# PS_DDR4.net
KiCad netlist of a schematic drawn in Altium Designer
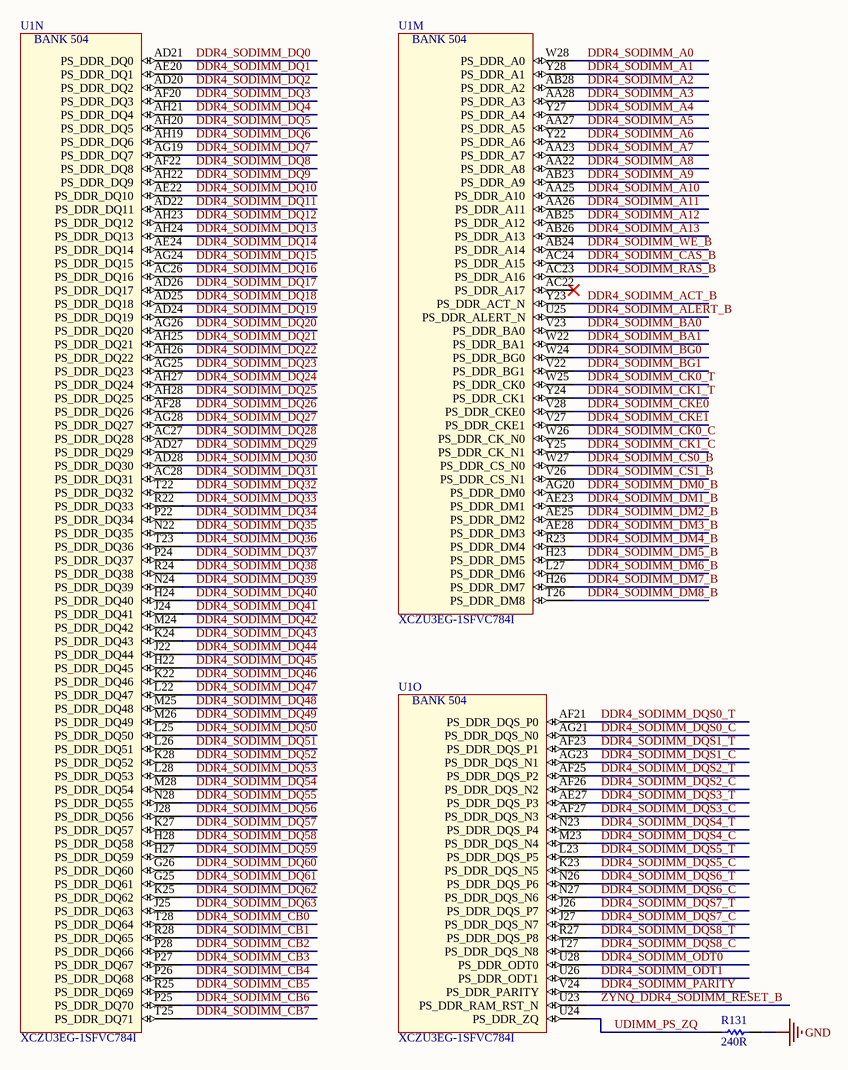
[diagram p0: PS_DDR4.SchDoc]

(export (version "E")
  (design (tool "Eeschema 10.0.6"))
  (components
    (comp (ref "R131")
      (value "240R")
      (footprint "RESC1005L_0402")
      (description "RES SMD 240 OHM 1% 1/10W 0402")
      (fields (field (name "POWER") "1/10W") (field (name "TOLERANCE") "1%"))
      (libsource (lib "Ultrascale_SchLib") (part "RES0402_240R_0W1_1T"))
    )
    (comp (ref "U1")
      (value "XCZU3EG-1SFVC784I")
      (footprint "BGA784x28")
      (description "IC FPGA 252 I/O 784FCBGA - XILINX ZYNQ ULTRASCALE+")
      (libsource (lib "Ultrascale_SchLib") (part "XCZU3EG-1SFVC784I"))
    )
  )
  (nets
    (net (code "1") (name "/DDR4_SODIMM_A0") (class "Default")
      (node (ref "U1") (pin "W28") (pinfunction "PS_DDR_A0_W28") (pintype "bidirectional"))
    )
    (net (code "2") (name "/DDR4_SODIMM_A1") (class "Default")
      (node (ref "U1") (pin "Y28") (pinfunction "PS_DDR_A1_Y28") (pintype "bidirectional"))
    )
    (net (code "3") (name "/DDR4_SODIMM_A2") (class "Default")
      (node (ref "U1") (pin "AB28") (pinfunction "PS_DDR_A2_AB28") (pintype "bidirectional"))
    )
    (net (code "4") (name "/DDR4_SODIMM_A3") (class "Default")
      (node (ref "U1") (pin "AA28") (pinfunction "PS_DDR_A3_AA28") (pintype "bidirectional"))
    )
    (net (code "5") (name "/DDR4_SODIMM_A4") (class "Default")
      (node (ref "U1") (pin "Y27") (pinfunction "PS_DDR_A4_Y27") (pintype "bidirectional"))
    )
    (net (code "6") (name "/DDR4_SODIMM_A5") (class "Default")
      (node (ref "U1") (pin "AA27") (pinfunction "PS_DDR_A5_AA27") (pintype "bidirectional"))
    )
    (net (code "7") (name "/DDR4_SODIMM_A6") (class "Default")
      (node (ref "U1") (pin "Y22") (pinfunction "PS_DDR_A6_Y22") (pintype "bidirectional"))
    )
    (net (code "8") (name "/DDR4_SODIMM_A7") (class "Default")
      (node (ref "U1") (pin "AA23") (pinfunction "PS_DDR_A7_AA23") (pintype "bidirectional"))
    )
    (net (code "9") (name "/DDR4_SODIMM_A8") (class "Default")
      (node (ref "U1") (pin "AA22") (pinfunction "PS_DDR_A8_AA22") (pintype "bidirectional"))
    )
    (net (code "10") (name "/DDR4_SODIMM_A9") (class "Default")
      (node (ref "U1") (pin "AB23") (pinfunction "PS_DDR_A9_AB23") (pintype "bidirectional"))
    )
    (net (code "11") (name "/DDR4_SODIMM_A10") (class "Default")
      (node (ref "U1") (pin "AA25") (pinfunction "PS_DDR_A10_AA25") (pintype "bidirectional"))
    )
    (net (code "12") (name "/DDR4_SODIMM_A11") (class "Default")
      (node (ref "U1") (pin "AA26") (pinfunction "PS_DDR_A11_AA26") (pintype "bidirectional"))
    )
    (net (code "13") (name "/DDR4_SODIMM_A12") (class "Default")
      (node (ref "U1") (pin "AB25") (pinfunction "PS_DDR_A12_AB25") (pintype "bidirectional"))
    )
    (net (code "14") (name "/DDR4_SODIMM_A13") (class "Default")
      (node (ref "U1") (pin "AB26") (pinfunction "PS_DDR_A13_AB26") (pintype "bidirectional"))
    )
    (net (code "15") (name "/DDR4_SODIMM_ACT_B") (class "Default")
      (node (ref "U1") (pin "Y23") (pinfunction "PS_DDR_ACT_N_Y23") (pintype "bidirectional"))
    )
    (net (code "16") (name "/DDR4_SODIMM_ALERT_B") (class "Default")
      (node (ref "U1") (pin "U25") (pinfunction "PS_DDR_ALERT_N_U25") (pintype "bidirectional"))
    )
    (net (code "17") (name "/DDR4_SODIMM_BA0") (class "Default")
      (node (ref "U1") (pin "V23") (pinfunction "PS_DDR_BA0_V23") (pintype "bidirectional"))
    )
    (net (code "18") (name "/DDR4_SODIMM_BA1") (class "Default")
      (node (ref "U1") (pin "W22") (pinfunction "PS_DDR_BA1_W22") (pintype "bidirectional"))
    )
    (net (code "19") (name "/DDR4_SODIMM_BG0") (class "Default")
      (node (ref "U1") (pin "W24") (pinfunction "PS_DDR_BG0_W24") (pintype "bidirectional"))
    )
    (net (code "20") (name "/DDR4_SODIMM_BG1") (class "Default")
      (node (ref "U1") (pin "V22") (pinfunction "PS_DDR_BG1_V22") (pintype "bidirectional"))
    )
    (net (code "21") (name "/DDR4_SODIMM_CAS_B") (class "Default")
      (node (ref "U1") (pin "AC24") (pinfunction "PS_DDR_A15_AC24") (pintype "bidirectional"))
    )
    (net (code "22") (name "/DDR4_SODIMM_CB0") (class "Default")
      (node (ref "U1") (pin "T28") (pinfunction "PS_DDR_DQ64_T28") (pintype "bidirectional"))
    )
    (net (code "23") (name "/DDR4_SODIMM_CB1") (class "Default")
      (node (ref "U1") (pin "R28") (pinfunction "PS_DDR_DQ65_R28") (pintype "bidirectional"))
    )
    (net (code "24") (name "/DDR4_SODIMM_CB2") (class "Default")
      (node (ref "U1") (pin "P28") (pinfunction "PS_DDR_DQ66_P28") (pintype "bidirectional"))
    )
    (net (code "25") (name "/DDR4_SODIMM_CB3") (class "Default")
      (node (ref "U1") (pin "P27") (pinfunction "PS_DDR_DQ67_P27") (pintype "bidirectional"))
    )
    (net (code "26") (name "/DDR4_SODIMM_CB4") (class "Default")
      (node (ref "U1") (pin "P26") (pinfunction "PS_DDR_DQ68_P26") (pintype "bidirectional"))
    )
    (net (code "27") (name "/DDR4_SODIMM_CB5") (class "Default")
      (node (ref "U1") (pin "R25") (pinfunction "PS_DDR_DQ69_R25") (pintype "bidirectional"))
    )
    (net (code "28") (name "/DDR4_SODIMM_CB6") (class "Default")
      (node (ref "U1") (pin "P25") (pinfunction "PS_DDR_DQ70_P25") (pintype "bidirectional"))
    )
    (net (code "29") (name "/DDR4_SODIMM_CB7") (class "Default")
      (node (ref "U1") (pin "T25") (pinfunction "PS_DDR_DQ71_T25") (pintype "bidirectional"))
    )
    (net (code "30") (name "/DDR4_SODIMM_CK0_C") (class "Default")
      (node (ref "U1") (pin "W26") (pinfunction "PS_DDR_CK_N0_W26") (pintype "bidirectional"))
    )
    (net (code "31") (name "/DDR4_SODIMM_CK0_T") (class "Default")
      (node (ref "U1") (pin "W25") (pinfunction "PS_DDR_CK0_W25") (pintype "bidirectional"))
    )
    (net (code "32") (name "/DDR4_SODIMM_CK1_C") (class "Default")
      (node (ref "U1") (pin "Y25") (pinfunction "PS_DDR_CK_N1_Y25") (pintype "bidirectional"))
    )
    (net (code "33") (name "/DDR4_SODIMM_CK1_T") (class "Default")
      (node (ref "U1") (pin "Y24") (pinfunction "PS_DDR_CK1_Y24") (pintype "bidirectional"))
    )
    (net (code "34") (name "/DDR4_SODIMM_CKE0") (class "Default")
      (node (ref "U1") (pin "V28") (pinfunction "PS_DDR_CKE0_V28") (pintype "bidirectional"))
    )
    (net (code "35") (name "/DDR4_SODIMM_CKE1") (class "Default")
      (node (ref "U1") (pin "V27") (pinfunction "PS_DDR_CKE1_V27") (pintype "bidirectional"))
    )
    (net (code "36") (name "/DDR4_SODIMM_CS0_B") (class "Default")
      (node (ref "U1") (pin "W27") (pinfunction "PS_DDR_CS_N0_W27") (pintype "bidirectional"))
    )
    (net (code "37") (name "/DDR4_SODIMM_CS1_B") (class "Default")
      (node (ref "U1") (pin "V26") (pinfunction "PS_DDR_CS_N1_V26") (pintype "bidirectional"))
    )
    (net (code "38") (name "/DDR4_SODIMM_DM0_B") (class "Default")
      (node (ref "U1") (pin "AG20") (pinfunction "PS_DDR_DM0_AG20") (pintype "bidirectional"))
    )
    (net (code "39") (name "/DDR4_SODIMM_DM1_B") (class "Default")
      (node (ref "U1") (pin "AE23") (pinfunction "PS_DDR_DM1_AE23") (pintype "bidirectional"))
    )
    (net (code "40") (name "/DDR4_SODIMM_DM2_B") (class "Default")
      (node (ref "U1") (pin "AE25") (pinfunction "PS_DDR_DM2_AE25") (pintype "bidirectional"))
    )
    (net (code "41") (name "/DDR4_SODIMM_DM3_B") (class "Default")
      (node (ref "U1") (pin "AE28") (pinfunction "PS_DDR_DM3_AE28") (pintype "bidirectional"))
    )
    (net (code "42") (name "/DDR4_SODIMM_DM4_B") (class "Default")
      (node (ref "U1") (pin "R23") (pinfunction "PS_DDR_DM4_R23") (pintype "bidirectional"))
    )
    (net (code "43") (name "/DDR4_SODIMM_DM5_B") (class "Default")
      (node (ref "U1") (pin "H23") (pinfunction "PS_DDR_DM5_H23") (pintype "bidirectional"))
    )
    (net (code "44") (name "/DDR4_SODIMM_DM6_B") (class "Default")
      (node (ref "U1") (pin "L27") (pinfunction "PS_DDR_DM6_L27") (pintype "bidirectional"))
    )
    (net (code "45") (name "/DDR4_SODIMM_DM7_B") (class "Default")
      (node (ref "U1") (pin "H26") (pinfunction "PS_DDR_DM7_H26") (pintype "bidirectional"))
    )
    (net (code "46") (name "/DDR4_SODIMM_DM8_B") (class "Default")
      (node (ref "U1") (pin "T26") (pinfunction "PS_DDR_DM8_T26") (pintype "bidirectional"))
    )
    (net (code "47") (name "/DDR4_SODIMM_DQ0") (class "Default")
      (node (ref "U1") (pin "AD21") (pinfunction "PS_DDR_DQ0_AD21") (pintype "bidirectional"))
    )
    (net (code "48") (name "/DDR4_SODIMM_DQ1") (class "Default")
      (node (ref "U1") (pin "AE20") (pinfunction "PS_DDR_DQ1_AE20") (pintype "bidirectional"))
    )
    (net (code "49") (name "/DDR4_SODIMM_DQ2") (class "Default")
      (node (ref "U1") (pin "AD20") (pinfunction "PS_DDR_DQ2_AD20") (pintype "bidirectional"))
    )
    (net (code "50") (name "/DDR4_SODIMM_DQ3") (class "Default")
      (node (ref "U1") (pin "AF20") (pinfunction "PS_DDR_DQ3_AF20") (pintype "bidirectional"))
    )
    (net (code "51") (name "/DDR4_SODIMM_DQ4") (class "Default")
      (node (ref "U1") (pin "AH21") (pinfunction "PS_DDR_DQ4_AH21") (pintype "bidirectional"))
    )
    (net (code "52") (name "/DDR4_SODIMM_DQ5") (class "Default")
      (node (ref "U1") (pin "AH20") (pinfunction "PS_DDR_DQ5_AH20") (pintype "bidirectional"))
    )
    (net (code "53") (name "/DDR4_SODIMM_DQ6") (class "Default")
      (node (ref "U1") (pin "AH19") (pinfunction "PS_DDR_DQ6_AH19") (pintype "bidirectional"))
    )
    (net (code "54") (name "/DDR4_SODIMM_DQ7") (class "Default")
      (node (ref "U1") (pin "AG19") (pinfunction "PS_DDR_DQ7_AG19") (pintype "bidirectional"))
    )
    (net (code "55") (name "/DDR4_SODIMM_DQ8") (class "Default")
      (node (ref "U1") (pin "AF22") (pinfunction "PS_DDR_DQ8_AF22") (pintype "bidirectional"))
    )
    (net (code "56") (name "/DDR4_SODIMM_DQ9") (class "Default")
      (node (ref "U1") (pin "AH22") (pinfunction "PS_DDR_DQ9_AH22") (pintype "bidirectional"))
    )
    (net (code "57") (name "/DDR4_SODIMM_DQ10") (class "Default")
      (node (ref "U1") (pin "AE22") (pinfunction "PS_DDR_DQ10_AE22") (pintype "bidirectional"))
    )
    (net (code "58") (name "/DDR4_SODIMM_DQ11") (class "Default")
      (node (ref "U1") (pin "AD22") (pinfunction "PS_DDR_DQ11_AD22") (pintype "bidirectional"))
    )
    (net (code "59") (name "/DDR4_SODIMM_DQ12") (class "Default")
      (node (ref "U1") (pin "AH23") (pinfunction "PS_DDR_DQ12_AH23") (pintype "bidirectional"))
    )
    (net (code "60") (name "/DDR4_SODIMM_DQ13") (class "Default")
      (node (ref "U1") (pin "AH24") (pinfunction "PS_DDR_DQ13_AH24") (pintype "bidirectional"))
    )
    (net (code "61") (name "/DDR4_SODIMM_DQ14") (class "Default")
      (node (ref "U1") (pin "AE24") (pinfunction "PS_DDR_DQ14_AE24") (pintype "bidirectional"))
    )
    (net (code "62") (name "/DDR4_SODIMM_DQ15") (class "Default")
      (node (ref "U1") (pin "AG24") (pinfunction "PS_DDR_DQ15_AG24") (pintype "bidirectional"))
    )
    (net (code "63") (name "/DDR4_SODIMM_DQ16") (class "Default")
      (node (ref "U1") (pin "AC26") (pinfunction "PS_DDR_DQ16_AC26") (pintype "bidirectional"))
    )
    (net (code "64") (name "/DDR4_SODIMM_DQ17") (class "Default")
      (node (ref "U1") (pin "AD26") (pinfunction "PS_DDR_DQ17_AD26") (pintype "bidirectional"))
    )
    (net (code "65") (name "/DDR4_SODIMM_DQ18") (class "Default")
      (node (ref "U1") (pin "AD25") (pinfunction "PS_DDR_DQ18_AD25") (pintype "bidirectional"))
    )
    (net (code "66") (name "/DDR4_SODIMM_DQ19") (class "Default")
      (node (ref "U1") (pin "AD24") (pinfunction "PS_DDR_DQ19_AD24") (pintype "bidirectional"))
    )
    (net (code "67") (name "/DDR4_SODIMM_DQ20") (class "Default")
      (node (ref "U1") (pin "AG26") (pinfunction "PS_DDR_DQ20_AG26") (pintype "bidirectional"))
    )
    (net (code "68") (name "/DDR4_SODIMM_DQ21") (class "Default")
      (node (ref "U1") (pin "AH25") (pinfunction "PS_DDR_DQ21_AH25") (pintype "bidirectional"))
    )
    (net (code "69") (name "/DDR4_SODIMM_DQ22") (class "Default")
      (node (ref "U1") (pin "AH26") (pinfunction "PS_DDR_DQ22_AH26") (pintype "bidirectional"))
    )
    (net (code "70") (name "/DDR4_SODIMM_DQ23") (class "Default")
      (node (ref "U1") (pin "AG25") (pinfunction "PS_DDR_DQ23_AG25") (pintype "bidirectional"))
    )
    (net (code "71") (name "/DDR4_SODIMM_DQ24") (class "Default")
      (node (ref "U1") (pin "AH27") (pinfunction "PS_DDR_DQ24_AH27") (pintype "bidirectional"))
    )
    (net (code "72") (name "/DDR4_SODIMM_DQ25") (class "Default")
      (node (ref "U1") (pin "AH28") (pinfunction "PS_DDR_DQ25_AH28") (pintype "bidirectional"))
    )
    (net (code "73") (name "/DDR4_SODIMM_DQ26") (class "Default")
      (node (ref "U1") (pin "AF28") (pinfunction "PS_DDR_DQ26_AF28") (pintype "bidirectional"))
    )
    (net (code "74") (name "/DDR4_SODIMM_DQ27") (class "Default")
      (node (ref "U1") (pin "AG28") (pinfunction "PS_DDR_DQ27_AG28") (pintype "bidirectional"))
    )
    (net (code "75") (name "/DDR4_SODIMM_DQ28") (class "Default")
      (node (ref "U1") (pin "AC27") (pinfunction "PS_DDR_DQ28_AC27") (pintype "bidirectional"))
    )
    (net (code "76") (name "/DDR4_SODIMM_DQ29") (class "Default")
      (node (ref "U1") (pin "AD27") (pinfunction "PS_DDR_DQ29_AD27") (pintype "bidirectional"))
    )
    (net (code "77") (name "/DDR4_SODIMM_DQ30") (class "Default")
      (node (ref "U1") (pin "AD28") (pinfunction "PS_DDR_DQ30_AD28") (pintype "bidirectional"))
    )
    (net (code "78") (name "/DDR4_SODIMM_DQ31") (class "Default")
      (node (ref "U1") (pin "AC28") (pinfunction "PS_DDR_DQ31_AC28") (pintype "bidirectional"))
    )
    (net (code "79") (name "/DDR4_SODIMM_DQ32") (class "Default")
      (node (ref "U1") (pin "T22") (pinfunction "PS_DDR_DQ32_T22") (pintype "bidirectional"))
    )
    (net (code "80") (name "/DDR4_SODIMM_DQ33") (class "Default")
      (node (ref "U1") (pin "R22") (pinfunction "PS_DDR_DQ33_R22") (pintype "bidirectional"))
    )
    (net (code "81") (name "/DDR4_SODIMM_DQ34") (class "Default")
      (node (ref "U1") (pin "P22") (pinfunction "PS_DDR_DQ34_P22") (pintype "bidirectional"))
    )
    (net (code "82") (name "/DDR4_SODIMM_DQ35") (class "Default")
      (node (ref "U1") (pin "N22") (pinfunction "PS_DDR_DQ35_N22") (pintype "bidirectional"))
    )
    (net (code "83") (name "/DDR4_SODIMM_DQ36") (class "Default")
      (node (ref "U1") (pin "T23") (pinfunction "PS_DDR_DQ36_T23") (pintype "bidirectional"))
    )
    (net (code "84") (name "/DDR4_SODIMM_DQ37") (class "Default")
      (node (ref "U1") (pin "P24") (pinfunction "PS_DDR_DQ37_P24") (pintype "bidirectional"))
    )
    (net (code "85") (name "/DDR4_SODIMM_DQ38") (class "Default")
      (node (ref "U1") (pin "R24") (pinfunction "PS_DDR_DQ38_R24") (pintype "bidirectional"))
    )
    (net (code "86") (name "/DDR4_SODIMM_DQ39") (class "Default")
      (node (ref "U1") (pin "N24") (pinfunction "PS_DDR_DQ39_N24") (pintype "bidirectional"))
    )
    (net (code "87") (name "/DDR4_SODIMM_DQ40") (class "Default")
      (node (ref "U1") (pin "H24") (pinfunction "PS_DDR_DQ40_H24") (pintype "bidirectional"))
    )
    (net (code "88") (name "/DDR4_SODIMM_DQ41") (class "Default")
      (node (ref "U1") (pin "J24") (pinfunction "PS_DDR_DQ41_J24") (pintype "bidirectional"))
    )
    (net (code "89") (name "/DDR4_SODIMM_DQ42") (class "Default")
      (node (ref "U1") (pin "M24") (pinfunction "PS_DDR_DQ42_M24") (pintype "bidirectional"))
    )
    (net (code "90") (name "/DDR4_SODIMM_DQ43") (class "Default")
      (node (ref "U1") (pin "K24") (pinfunction "PS_DDR_DQ43_K24") (pintype "bidirectional"))
    )
    (net (code "91") (name "/DDR4_SODIMM_DQ44") (class "Default")
      (node (ref "U1") (pin "J22") (pinfunction "PS_DDR_DQ44_J22") (pintype "bidirectional"))
    )
    (net (code "92") (name "/DDR4_SODIMM_DQ45") (class "Default")
      (node (ref "U1") (pin "H22") (pinfunction "PS_DDR_DQ45_H22") (pintype "bidirectional"))
    )
    (net (code "93") (name "/DDR4_SODIMM_DQ46") (class "Default")
      (node (ref "U1") (pin "K22") (pinfunction "PS_DDR_DQ46_K22") (pintype "bidirectional"))
    )
    (net (code "94") (name "/DDR4_SODIMM_DQ47") (class "Default")
      (node (ref "U1") (pin "L22") (pinfunction "PS_DDR_DQ47_L22") (pintype "bidirectional"))
    )
    (net (code "95") (name "/DDR4_SODIMM_DQ48") (class "Default")
      (node (ref "U1") (pin "M25") (pinfunction "PS_DDR_DQ48_M25") (pintype "bidirectional"))
    )
    (net (code "96") (name "/DDR4_SODIMM_DQ49") (class "Default")
      (node (ref "U1") (pin "M26") (pinfunction "PS_DDR_DQ49_M26") (pintype "bidirectional"))
    )
    (net (code "97") (name "/DDR4_SODIMM_DQ50") (class "Default")
      (node (ref "U1") (pin "L25") (pinfunction "PS_DDR_DQ50_L25") (pintype "bidirectional"))
    )
    (net (code "98") (name "/DDR4_SODIMM_DQ51") (class "Default")
      (node (ref "U1") (pin "L26") (pinfunction "PS_DDR_DQ51_L26") (pintype "bidirectional"))
    )
    (net (code "99") (name "/DDR4_SODIMM_DQ52") (class "Default")
      (node (ref "U1") (pin "K28") (pinfunction "PS_DDR_DQ52_K28") (pintype "bidirectional"))
    )
    (net (code "100") (name "/DDR4_SODIMM_DQ53") (class "Default")
      (node (ref "U1") (pin "L28") (pinfunction "PS_DDR_DQ53_L28") (pintype "bidirectional"))
    )
    (net (code "101") (name "/DDR4_SODIMM_DQ54") (class "Default")
      (node (ref "U1") (pin "M28") (pinfunction "PS_DDR_DQ54_M28") (pintype "bidirectional"))
    )
    (net (code "102") (name "/DDR4_SODIMM_DQ55") (class "Default")
      (node (ref "U1") (pin "N28") (pinfunction "PS_DDR_DQ55_N28") (pintype "bidirectional"))
    )
    (net (code "103") (name "/DDR4_SODIMM_DQ56") (class "Default")
      (node (ref "U1") (pin "J28") (pinfunction "PS_DDR_DQ56_J28") (pintype "bidirectional"))
    )
    (net (code "104") (name "/DDR4_SODIMM_DQ57") (class "Default")
      (node (ref "U1") (pin "K27") (pinfunction "PS_DDR_DQ57_K27") (pintype "bidirectional"))
    )
    (net (code "105") (name "/DDR4_SODIMM_DQ58") (class "Default")
      (node (ref "U1") (pin "H28") (pinfunction "PS_DDR_DQ58_H28") (pintype "bidirectional"))
    )
    (net (code "106") (name "/DDR4_SODIMM_DQ59") (class "Default")
      (node (ref "U1") (pin "H27") (pinfunction "PS_DDR_DQ59_H27") (pintype "bidirectional"))
    )
    (net (code "107") (name "/DDR4_SODIMM_DQ60") (class "Default")
      (node (ref "U1") (pin "G26") (pinfunction "PS_DDR_DQ60_G26") (pintype "bidirectional"))
    )
    (net (code "108") (name "/DDR4_SODIMM_DQ61") (class "Default")
      (node (ref "U1") (pin "G25") (pinfunction "PS_DDR_DQ61_G25") (pintype "bidirectional"))
    )
    (net (code "109") (name "/DDR4_SODIMM_DQ62") (class "Default")
      (node (ref "U1") (pin "K25") (pinfunction "PS_DDR_DQ62_K25") (pintype "bidirectional"))
    )
    (net (code "110") (name "/DDR4_SODIMM_DQ63") (class "Default")
      (node (ref "U1") (pin "J25") (pinfunction "PS_DDR_DQ63_J25") (pintype "bidirectional"))
    )
    (net (code "111") (name "/DDR4_SODIMM_DQS0_C") (class "Default")
      (node (ref "U1") (pin "AG21") (pinfunction "PS_DDR_DQS_N0_AG21") (pintype "bidirectional"))
    )
    (net (code "112") (name "/DDR4_SODIMM_DQS0_T") (class "Default")
      (node (ref "U1") (pin "AF21") (pinfunction "PS_DDR_DQS_P0_AF21") (pintype "bidirectional"))
    )
    (net (code "113") (name "/DDR4_SODIMM_DQS1_C") (class "Default")
      (node (ref "U1") (pin "AG23") (pinfunction "PS_DDR_DQS_N1_AG23") (pintype "bidirectional"))
    )
    (net (code "114") (name "/DDR4_SODIMM_DQS1_T") (class "Default")
      (node (ref "U1") (pin "AF23") (pinfunction "PS_DDR_DQS_P1_AF23") (pintype "bidirectional"))
    )
    (net (code "115") (name "/DDR4_SODIMM_DQS2_C") (class "Default")
      (node (ref "U1") (pin "AF26") (pinfunction "PS_DDR_DQS_N2_AF26") (pintype "bidirectional"))
    )
    (net (code "116") (name "/DDR4_SODIMM_DQS2_T") (class "Default")
      (node (ref "U1") (pin "AF25") (pinfunction "PS_DDR_DQS_P2_AF25") (pintype "bidirectional"))
    )
    (net (code "117") (name "/DDR4_SODIMM_DQS3_C") (class "Default")
      (node (ref "U1") (pin "AF27") (pinfunction "PS_DDR_DQS_N3_AF27") (pintype "bidirectional"))
    )
    (net (code "118") (name "/DDR4_SODIMM_DQS3_T") (class "Default")
      (node (ref "U1") (pin "AE27") (pinfunction "PS_DDR_DQS_P3_AE27") (pintype "bidirectional"))
    )
    (net (code "119") (name "/DDR4_SODIMM_DQS4_C") (class "Default")
      (node (ref "U1") (pin "M23") (pinfunction "PS_DDR_DQS_N4_M23") (pintype "bidirectional"))
    )
    (net (code "120") (name "/DDR4_SODIMM_DQS4_T") (class "Default")
      (node (ref "U1") (pin "N23") (pinfunction "PS_DDR_DQS_P4_N23") (pintype "bidirectional"))
    )
    (net (code "121") (name "/DDR4_SODIMM_DQS5_C") (class "Default")
      (node (ref "U1") (pin "K23") (pinfunction "PS_DDR_DQS_N5_K23") (pintype "bidirectional"))
    )
    (net (code "122") (name "/DDR4_SODIMM_DQS5_T") (class "Default")
      (node (ref "U1") (pin "L23") (pinfunction "PS_DDR_DQS_P5_L23") (pintype "bidirectional"))
    )
    (net (code "123") (name "/DDR4_SODIMM_DQS6_C") (class "Default")
      (node (ref "U1") (pin "N27") (pinfunction "PS_DDR_DQS_N6_N27") (pintype "bidirectional"))
    )
    (net (code "124") (name "/DDR4_SODIMM_DQS6_T") (class "Default")
      (node (ref "U1") (pin "N26") (pinfunction "PS_DDR_DQS_P6_N26") (pintype "bidirectional"))
    )
    (net (code "125") (name "/DDR4_SODIMM_DQS7_C") (class "Default")
      (node (ref "U1") (pin "J27") (pinfunction "PS_DDR_DQS_N7_J27") (pintype "bidirectional"))
    )
    (net (code "126") (name "/DDR4_SODIMM_DQS7_T") (class "Default")
      (node (ref "U1") (pin "J26") (pinfunction "PS_DDR_DQS_P7_J26") (pintype "bidirectional"))
    )
    (net (code "127") (name "/DDR4_SODIMM_DQS8_C") (class "Default")
      (node (ref "U1") (pin "T27") (pinfunction "PS_DDR_DQS_N8_T27") (pintype "bidirectional"))
    )
    (net (code "128") (name "/DDR4_SODIMM_DQS8_T") (class "Default")
      (node (ref "U1") (pin "R27") (pinfunction "PS_DDR_DQS_P8_R27") (pintype "bidirectional"))
    )
    (net (code "129") (name "/DDR4_SODIMM_ODT0") (class "Default")
      (node (ref "U1") (pin "U28") (pinfunction "PS_DDR_ODT0_U28") (pintype "bidirectional"))
    )
    (net (code "130") (name "/DDR4_SODIMM_ODT1") (class "Default")
      (node (ref "U1") (pin "U26") (pinfunction "PS_DDR_ODT1_U26") (pintype "bidirectional"))
    )
    (net (code "131") (name "/DDR4_SODIMM_PARITY") (class "Default")
      (node (ref "U1") (pin "V24") (pinfunction "PS_DDR_PARITY_V24") (pintype "bidirectional"))
    )
    (net (code "132") (name "/DDR4_SODIMM_RAS_B") (class "Default")
      (node (ref "U1") (pin "AC23") (pinfunction "PS_DDR_A16_AC23") (pintype "bidirectional"))
    )
    (net (code "133") (name "/DDR4_SODIMM_WE_B") (class "Default")
      (node (ref "U1") (pin "AB24") (pinfunction "PS_DDR_A14_AB24") (pintype "bidirectional"))
    )
    (net (code "134") (name "/UDIMM_PS_ZQ") (class "Default")
      (node (ref "R131") (pin "2") (pinfunction "2_2") (pintype "passive"))
      (node (ref "U1") (pin "U24") (pinfunction "PS_DDR_ZQ_U24") (pintype "bidirectional"))
    )
    (net (code "135") (name "/ZYNQ_DDR4_SODIMM_RESET_B") (class "Default")
      (node (ref "U1") (pin "U23") (pinfunction "PS_DDR_RAM_RST_N_U23") (pintype "bidirectional"))
    )
    (net (code "136") (name "GND") (class "Default")
      (node (ref "R131") (pin "1") (pinfunction "1_1") (pintype "passive"))
    )
    (net (code "137") (name "unconnected-(U1M-PS_DDR_A17-PadAC22)") (class "Default")
      (node (ref "U1") (pin "AC22") (pinfunction "PS_DDR_A17_AC22") (pintype "bidirectional+no_connect"))
    )
  )
)
